# Key_PCB.net
KiCad netlist of a schematic drawn in EAGLE
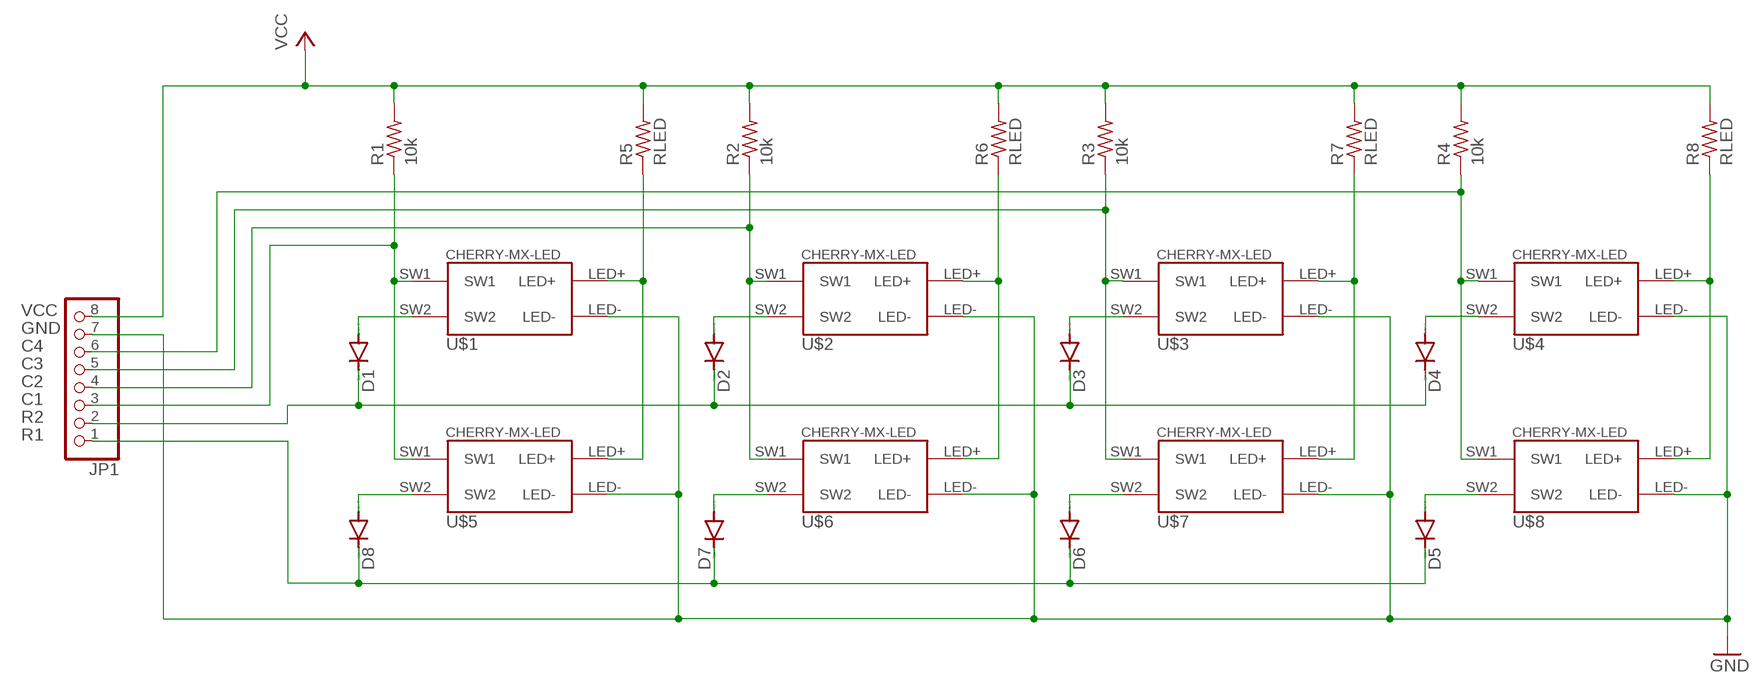
[diagram p0: schematic, sheet 1]

(export (version "E")
  (design (tool "Eeschema 10.0.6"))
  (components
    (comp (ref "D1")
      (value "1N4148DO35-7")
      (footprint "eagle-import:DO35-7")
      (libsource (lib "eagle-import") (part "1N4148DO35-7"))
    )
    (comp (ref "D2")
      (value "1N4148DO35-7")
      (footprint "eagle-import:DO35-7")
      (libsource (lib "eagle-import") (part "1N4148DO35-7"))
    )
    (comp (ref "D3")
      (value "1N4148DO35-7")
      (footprint "eagle-import:DO35-7")
      (libsource (lib "eagle-import") (part "1N4148DO35-7"))
    )
    (comp (ref "D4")
      (value "1N4148DO35-7")
      (footprint "eagle-import:DO35-7")
      (libsource (lib "eagle-import") (part "1N4148DO35-7"))
    )
    (comp (ref "D5")
      (value "1N4148DO35-7")
      (footprint "eagle-import:DO35-7")
      (libsource (lib "eagle-import") (part "1N4148DO35-7"))
    )
    (comp (ref "D6")
      (value "1N4148DO35-7")
      (footprint "eagle-import:DO35-7")
      (libsource (lib "eagle-import") (part "1N4148DO35-7"))
    )
    (comp (ref "D7")
      (value "1N4148DO35-7")
      (footprint "eagle-import:DO35-7")
      (libsource (lib "eagle-import") (part "1N4148DO35-7"))
    )
    (comp (ref "D8")
      (value "1N4148DO35-7")
      (footprint "eagle-import:DO35-7")
      (libsource (lib "eagle-import") (part "1N4148DO35-7"))
    )
    (comp (ref "JP1")
      (value "PINHD-1X8")
      (footprint "eagle-import:1X08")
      (libsource (lib "eagle-import") (part "PINHD-1X8"))
    )
    (comp (ref "R1")
      (value "10k")
      (footprint "eagle-import:0207_10")
      (libsource (lib "eagle-import") (part "R-US_0207/10"))
    )
    (comp (ref "R2")
      (value "10k")
      (footprint "eagle-import:0207_10")
      (libsource (lib "eagle-import") (part "R-US_0207/10"))
    )
    (comp (ref "R3")
      (value "10k")
      (footprint "eagle-import:0207_10")
      (libsource (lib "eagle-import") (part "R-US_0207/10"))
    )
    (comp (ref "R4")
      (value "10k")
      (footprint "eagle-import:0207_10")
      (libsource (lib "eagle-import") (part "R-US_0207/10"))
    )
    (comp (ref "R5")
      (value "RLED")
      (footprint "eagle-import:0207_10")
      (libsource (lib "eagle-import") (part "R-US_0207/10"))
    )
    (comp (ref "R6")
      (value "RLED")
      (footprint "eagle-import:0207_10")
      (libsource (lib "eagle-import") (part "R-US_0207/10"))
    )
    (comp (ref "R7")
      (value "RLED")
      (footprint "eagle-import:0207_10")
      (libsource (lib "eagle-import") (part "R-US_0207/10"))
    )
    (comp (ref "R8")
      (value "RLED")
      (footprint "eagle-import:0207_10")
      (libsource (lib "eagle-import") (part "R-US_0207/10"))
    )
    (comp (ref "U$1")
      (value "CHERRY-MX-LED")
      (footprint "eagle-import:CHERRY-MX-LED")
      (libsource (lib "eagle-import") (part "CHERRY-MX-LED"))
    )
    (comp (ref "U$2")
      (value "CHERRY-MX-LED")
      (footprint "eagle-import:CHERRY-MX-LED")
      (libsource (lib "eagle-import") (part "CHERRY-MX-LED"))
    )
    (comp (ref "U$3")
      (value "CHERRY-MX-LED")
      (footprint "eagle-import:CHERRY-MX-LED")
      (libsource (lib "eagle-import") (part "CHERRY-MX-LED"))
    )
    (comp (ref "U$4")
      (value "CHERRY-MX-LED")
      (footprint "eagle-import:CHERRY-MX-LED")
      (libsource (lib "eagle-import") (part "CHERRY-MX-LED"))
    )
    (comp (ref "U$5")
      (value "CHERRY-MX-LED")
      (footprint "eagle-import:CHERRY-MX-LED")
      (libsource (lib "eagle-import") (part "CHERRY-MX-LED"))
    )
    (comp (ref "U$6")
      (value "CHERRY-MX-LED")
      (footprint "eagle-import:CHERRY-MX-LED")
      (libsource (lib "eagle-import") (part "CHERRY-MX-LED"))
    )
    (comp (ref "U$7")
      (value "CHERRY-MX-LED")
      (footprint "eagle-import:CHERRY-MX-LED")
      (libsource (lib "eagle-import") (part "CHERRY-MX-LED"))
    )
    (comp (ref "U$8")
      (value "CHERRY-MX-LED")
      (footprint "eagle-import:CHERRY-MX-LED")
      (libsource (lib "eagle-import") (part "CHERRY-MX-LED"))
    )
  )
  (nets
    (net (code "1") (name "/C1") (class "Default")
      (node (ref "JP1") (pin "3") (pinfunction "3_3") (pintype "passive"))
      (node (ref "R1") (pin "1") (pinfunction "1_1") (pintype "passive"))
      (node (ref "U$1") (pin "SW1") (pinfunction "SW1_SW1") (pintype "bidirectional"))
      (node (ref "U$5") (pin "SW1") (pinfunction "SW1_SW1") (pintype "bidirectional"))
    )
    (net (code "2") (name "/C2") (class "Default")
      (node (ref "JP1") (pin "4") (pinfunction "4_4") (pintype "passive"))
      (node (ref "R2") (pin "1") (pinfunction "1_1") (pintype "passive"))
      (node (ref "U$2") (pin "SW1") (pinfunction "SW1_SW1") (pintype "bidirectional"))
      (node (ref "U$6") (pin "SW1") (pinfunction "SW1_SW1") (pintype "bidirectional"))
    )
    (net (code "3") (name "/C3") (class "Default")
      (node (ref "JP1") (pin "5") (pinfunction "5_5") (pintype "passive"))
      (node (ref "R3") (pin "1") (pinfunction "1_1") (pintype "passive"))
      (node (ref "U$3") (pin "SW1") (pinfunction "SW1_SW1") (pintype "bidirectional"))
      (node (ref "U$7") (pin "SW1") (pinfunction "SW1_SW1") (pintype "bidirectional"))
    )
    (net (code "4") (name "/C4") (class "Default")
      (node (ref "JP1") (pin "6") (pinfunction "6_6") (pintype "passive"))
      (node (ref "R4") (pin "1") (pinfunction "1_1") (pintype "passive"))
      (node (ref "U$4") (pin "SW1") (pinfunction "SW1_SW1") (pintype "bidirectional"))
      (node (ref "U$8") (pin "SW1") (pinfunction "SW1_SW1") (pintype "bidirectional"))
    )
    (net (code "5") (name "/R1") (class "Default")
      (node (ref "D5") (pin "C") (pinfunction "C_C") (pintype "passive"))
      (node (ref "D6") (pin "C") (pinfunction "C_C") (pintype "passive"))
      (node (ref "D7") (pin "C") (pinfunction "C_C") (pintype "passive"))
      (node (ref "D8") (pin "C") (pinfunction "C_C") (pintype "passive"))
      (node (ref "JP1") (pin "1") (pinfunction "1_1") (pintype "passive"))
    )
    (net (code "6") (name "/R2") (class "Default")
      (node (ref "D1") (pin "C") (pinfunction "C_C") (pintype "passive"))
      (node (ref "D2") (pin "C") (pinfunction "C_C") (pintype "passive"))
      (node (ref "D3") (pin "C") (pinfunction "C_C") (pintype "passive"))
      (node (ref "D4") (pin "C") (pinfunction "C_C") (pintype "passive"))
      (node (ref "JP1") (pin "2") (pinfunction "2_2") (pintype "passive"))
    )
    (net (code "7") (name "GND") (class "Default")
      (node (ref "JP1") (pin "7") (pinfunction "7_7") (pintype "passive"))
      (node (ref "U$1") (pin "LED-") (pinfunction "LED-_LED-") (pintype "bidirectional"))
      (node (ref "U$2") (pin "LED-") (pinfunction "LED-_LED-") (pintype "bidirectional"))
      (node (ref "U$3") (pin "LED-") (pinfunction "LED-_LED-") (pintype "bidirectional"))
      (node (ref "U$4") (pin "LED-") (pinfunction "LED-_LED-") (pintype "bidirectional"))
      (node (ref "U$5") (pin "LED-") (pinfunction "LED-_LED-") (pintype "bidirectional"))
      (node (ref "U$6") (pin "LED-") (pinfunction "LED-_LED-") (pintype "bidirectional"))
      (node (ref "U$7") (pin "LED-") (pinfunction "LED-_LED-") (pintype "bidirectional"))
      (node (ref "U$8") (pin "LED-") (pinfunction "LED-_LED-") (pintype "bidirectional"))
    )
    (net (code "8") (name "Net-(D1-PadA)") (class "Default")
      (node (ref "D1") (pin "A") (pinfunction "A_A") (pintype "passive"))
      (node (ref "U$1") (pin "SW2") (pinfunction "SW2_SW2") (pintype "bidirectional"))
    )
    (net (code "9") (name "Net-(D2-PadA)") (class "Default")
      (node (ref "D2") (pin "A") (pinfunction "A_A") (pintype "passive"))
      (node (ref "U$2") (pin "SW2") (pinfunction "SW2_SW2") (pintype "bidirectional"))
    )
    (net (code "10") (name "Net-(D3-PadA)") (class "Default")
      (node (ref "D3") (pin "A") (pinfunction "A_A") (pintype "passive"))
      (node (ref "U$3") (pin "SW2") (pinfunction "SW2_SW2") (pintype "bidirectional"))
    )
    (net (code "11") (name "Net-(D4-PadA)") (class "Default")
      (node (ref "D4") (pin "A") (pinfunction "A_A") (pintype "passive"))
      (node (ref "U$4") (pin "SW2") (pinfunction "SW2_SW2") (pintype "bidirectional"))
    )
    (net (code "12") (name "Net-(D5-PadA)") (class "Default")
      (node (ref "D5") (pin "A") (pinfunction "A_A") (pintype "passive"))
      (node (ref "U$8") (pin "SW2") (pinfunction "SW2_SW2") (pintype "bidirectional"))
    )
    (net (code "13") (name "Net-(D6-PadA)") (class "Default")
      (node (ref "D6") (pin "A") (pinfunction "A_A") (pintype "passive"))
      (node (ref "U$7") (pin "SW2") (pinfunction "SW2_SW2") (pintype "bidirectional"))
    )
    (net (code "14") (name "Net-(D7-PadA)") (class "Default")
      (node (ref "D7") (pin "A") (pinfunction "A_A") (pintype "passive"))
      (node (ref "U$6") (pin "SW2") (pinfunction "SW2_SW2") (pintype "bidirectional"))
    )
    (net (code "15") (name "Net-(D8-PadA)") (class "Default")
      (node (ref "D8") (pin "A") (pinfunction "A_A") (pintype "passive"))
      (node (ref "U$5") (pin "SW2") (pinfunction "SW2_SW2") (pintype "bidirectional"))
    )
    (net (code "16") (name "Net-(R5-Pad1)") (class "Default")
      (node (ref "R5") (pin "1") (pinfunction "1_1") (pintype "passive"))
      (node (ref "U$1") (pin "LED+") (pinfunction "LED+_LED+") (pintype "bidirectional"))
      (node (ref "U$5") (pin "LED+") (pinfunction "LED+_LED+") (pintype "bidirectional"))
    )
    (net (code "17") (name "Net-(R6-Pad1)") (class "Default")
      (node (ref "R6") (pin "1") (pinfunction "1_1") (pintype "passive"))
      (node (ref "U$2") (pin "LED+") (pinfunction "LED+_LED+") (pintype "bidirectional"))
      (node (ref "U$6") (pin "LED+") (pinfunction "LED+_LED+") (pintype "bidirectional"))
    )
    (net (code "18") (name "Net-(R7-Pad1)") (class "Default")
      (node (ref "R7") (pin "1") (pinfunction "1_1") (pintype "passive"))
      (node (ref "U$3") (pin "LED+") (pinfunction "LED+_LED+") (pintype "bidirectional"))
      (node (ref "U$7") (pin "LED+") (pinfunction "LED+_LED+") (pintype "bidirectional"))
    )
    (net (code "19") (name "Net-(R8-Pad1)") (class "Default")
      (node (ref "R8") (pin "1") (pinfunction "1_1") (pintype "passive"))
      (node (ref "U$4") (pin "LED+") (pinfunction "LED+_LED+") (pintype "bidirectional"))
      (node (ref "U$8") (pin "LED+") (pinfunction "LED+_LED+") (pintype "bidirectional"))
    )
    (net (code "20") (name "VCC") (class "Default")
      (node (ref "JP1") (pin "8") (pinfunction "8_8") (pintype "passive"))
      (node (ref "R1") (pin "2") (pinfunction "2_2") (pintype "passive"))
      (node (ref "R2") (pin "2") (pinfunction "2_2") (pintype "passive"))
      (node (ref "R3") (pin "2") (pinfunction "2_2") (pintype "passive"))
      (node (ref "R4") (pin "2") (pinfunction "2_2") (pintype "passive"))
      (node (ref "R5") (pin "2") (pinfunction "2_2") (pintype "passive"))
      (node (ref "R6") (pin "2") (pinfunction "2_2") (pintype "passive"))
      (node (ref "R7") (pin "2") (pinfunction "2_2") (pintype "passive"))
      (node (ref "R8") (pin "2") (pinfunction "2_2") (pintype "passive"))
    )
  )
)
